# AMU-S05-V00-CAN2.net
KiCad netlist of a schematic drawn in Altium Designer
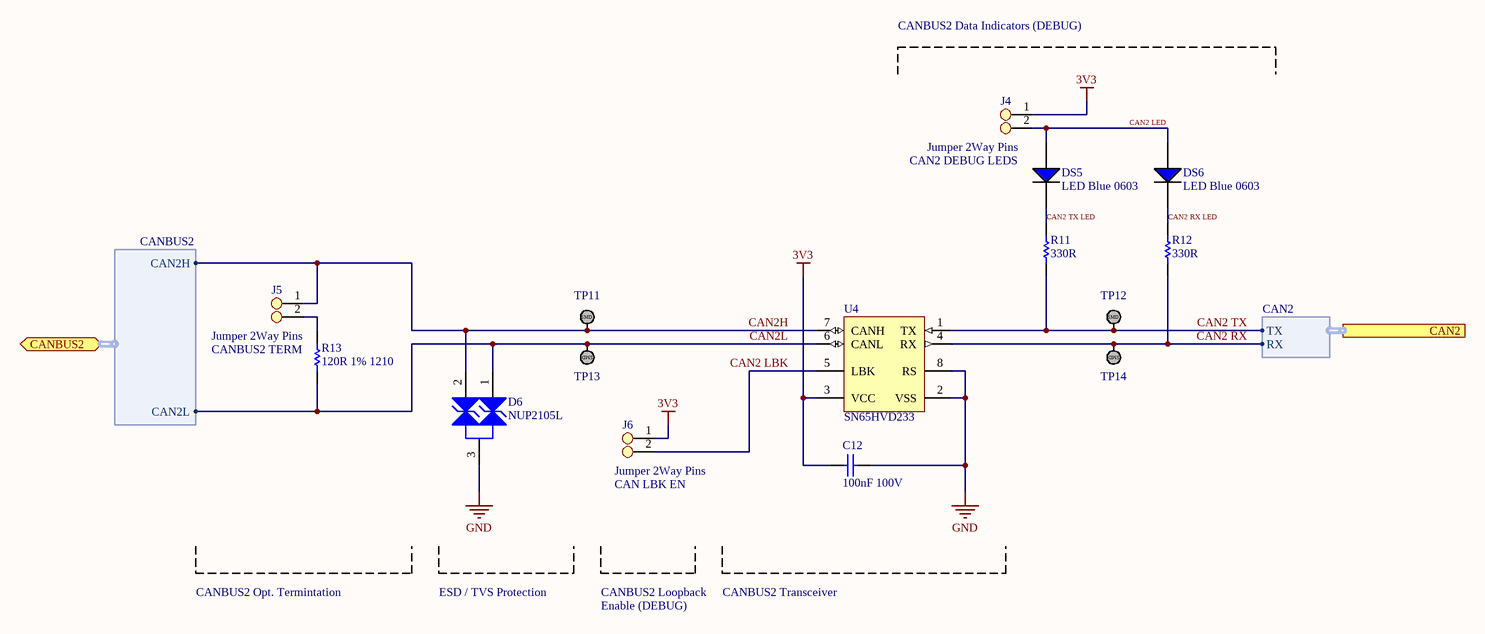
[diagram p0: AMU-S05-V00-CAN2.SchDoc]

(export (version "E")
  (design (tool "Eeschema 10.0.6"))
  (components
    (comp (ref "C12")
      (value "100nF 100V")
      (footprint "Cap_Ceramic_0603")
      (description "Capacitor, Ceramic, SMD, 100nF, 100V, 5%, X7R, 0603")
      (libsource (lib "StandardCapacitors") (part "100nF 100V 5% X7R 0603"))
    )
    (comp (ref "D6")
      (value "NUP2105L")
      (footprint "NUP2105L")
      (libsource (lib "QUTMS_CANLibrary") (part "NUP2105L"))
    )
    (comp (ref "DS5")
      (value "LED Blue 0603")
      (footprint "LED BLUE 0603")
      (libsource (lib "QUTMS_LEDLibrary") (part "LED BLUE 0603"))
    )
    (comp (ref "DS6")
      (value "LED Blue 0603")
      (footprint "LED BLUE 0603")
      (libsource (lib "QUTMS_LEDLibrary") (part "LED BLUE 0603"))
    )
    (comp (ref "J4")
      (value "Jumper 2Way Pins")
      (footprint "Jumper_2Way_Pin")
      (description "Jumper 2Way Side Pins")
      (libsource (lib "QUTMS_JumperLibrary") (part "Jumper 2Way Side Pins"))
    )
    (comp (ref "J5")
      (value "Jumper 2Way Pins")
      (footprint "Jumper_2Way_Pin")
      (description "Jumper 2Way Side Pins")
      (libsource (lib "QUTMS_JumperLibrary") (part "Jumper 2Way Side Pins"))
    )
    (comp (ref "J6")
      (value "Jumper 2Way Pins")
      (footprint "Jumper_2Way_Pin")
      (description "Jumper 2Way Side Pins")
      (libsource (lib "QUTMS_JumperLibrary") (part "Jumper 2Way Side Pins"))
    )
    (comp (ref "R11")
      (value "330R")
      (footprint "Res_ThinFilm_0603")
      (description "Resistor, SMD, 330R, 0.1W, 5%, 0603")
      (libsource (lib "StandardResistors") (part "330R 5% 0603"))
    )
    (comp (ref "R12")
      (value "330R")
      (footprint "Res_ThinFilm_0603")
      (description "Resistor, SMD, 330R, 0.1W, 5%, 0603")
      (libsource (lib "StandardResistors") (part "330R 5% 0603"))
    )
    (comp (ref "R13")
      (value "120R 1% 1210")
      (footprint "Res_ThinFilm_1210")
      (description "Resistor, SMD, 120R, 0.25W, 1%, 1210")
      (libsource (lib "StandardResistors") (part "120R 1% 1210"))
    )
    (comp (ref "TP11")
      (value "TestPoint_SMD")
      (footprint "TestPointSMD")
      (libsource (lib "StandardTest") (part "TestPoint_SMD"))
    )
    (comp (ref "TP12")
      (value "TestPoint_SMD")
      (footprint "TestPointSMD")
      (libsource (lib "StandardTest") (part "TestPoint_SMD"))
    )
    (comp (ref "TP13")
      (value "TestPoint_SMD")
      (footprint "TestPointSMD")
      (libsource (lib "StandardTest") (part "TestPoint_SMD"))
    )
    (comp (ref "TP14")
      (value "TestPoint_SMD")
      (footprint "TestPointSMD")
      (libsource (lib "StandardTest") (part "TestPoint_SMD"))
    )
    (comp (ref "U4")
      (value "SN65HVD233")
      (footprint "SN65HVD233DR")
      (libsource (lib "QUTMS_CANLibrary") (part "SN65HVD233"))
    )
  )
  (nets
    (net (code "3") (name "/CAN2 LBK") (class "Default")
      (node (ref "J6") (pin "2") (pinfunction "2_2") (pintype "passive"))
      (node (ref "U4") (pin "5") (pinfunction "LBK_5") (pintype "passive"))
    )
    (net (code "4") (name "/CAN2 LED") (class "Default")
      (node (ref "DS5") (pin "1") (pinfunction "A_1") (pintype "passive"))
      (node (ref "DS6") (pin "1") (pinfunction "A_1") (pintype "passive"))
      (node (ref "J4") (pin "2") (pinfunction "2_2") (pintype "passive"))
    )
    (net (code "5") (name "/CAN2 RX") (class "Default")
      (node (ref "R12") (pin "1") (pinfunction "1_1") (pintype "passive"))
      (node (ref "TP14") (pin "1") (pinfunction "1_1") (pintype "passive"))
      (node (ref "U4") (pin "4") (pinfunction "RX_4") (pintype "output"))
    )
    (net (code "6") (name "/CAN2 RX LED") (class "Default")
      (node (ref "DS6") (pin "2") (pinfunction "C_2") (pintype "passive"))
      (node (ref "R12") (pin "2") (pinfunction "2_2") (pintype "passive"))
    )
    (net (code "7") (name "/CAN2 TX") (class "Default")
      (node (ref "R11") (pin "1") (pinfunction "1_1") (pintype "passive"))
      (node (ref "TP12") (pin "1") (pinfunction "1_1") (pintype "passive"))
      (node (ref "U4") (pin "1") (pinfunction "TX_1") (pintype "input"))
    )
    (net (code "8") (name "/CAN2 TX LED") (class "Default")
      (node (ref "DS5") (pin "2") (pinfunction "C_2") (pintype "passive"))
      (node (ref "R11") (pin "2") (pinfunction "2_2") (pintype "passive"))
    )
    (net (code "9") (name "/CAN2H") (class "Default")
      (node (ref "D6") (pin "2") (pinfunction "2_2") (pintype "passive"))
      (node (ref "J5") (pin "1") (pinfunction "1_1") (pintype "passive"))
      (node (ref "TP11") (pin "1") (pinfunction "1_1") (pintype "passive"))
      (node (ref "U4") (pin "7") (pinfunction "CANH_7") (pintype "bidirectional"))
    )
    (net (code "10") (name "/CAN2L") (class "Default")
      (node (ref "D6") (pin "1") (pinfunction "1_1") (pintype "passive"))
      (node (ref "R13") (pin "1") (pinfunction "1_1") (pintype "passive"))
      (node (ref "TP13") (pin "1") (pinfunction "1_1") (pintype "passive"))
      (node (ref "U4") (pin "6") (pinfunction "CANL_6") (pintype "bidirectional"))
    )
    (net (code "13") (name "3V3") (class "Default")
      (node (ref "C12") (pin "2") (pinfunction "2_2") (pintype "passive"))
      (node (ref "J4") (pin "1") (pinfunction "1_1") (pintype "passive"))
      (node (ref "J6") (pin "1") (pinfunction "1_1") (pintype "passive"))
      (node (ref "U4") (pin "3") (pinfunction "VCC_3") (pintype "passive"))
    )
    (net (code "14") (name "GND") (class "Default")
      (node (ref "C12") (pin "1") (pinfunction "1_1") (pintype "passive"))
      (node (ref "D6") (pin "3") (pinfunction "3_3") (pintype "passive"))
      (node (ref "U4") (pin "2") (pinfunction "VSS_2") (pintype "passive"))
      (node (ref "U4") (pin "8") (pinfunction "RS_8") (pintype "passive"))
    )
    (net (code "15") (name "Net-(J5-Pad2)") (class "Default")
      (node (ref "J5") (pin "2") (pinfunction "2_2") (pintype "passive"))
      (node (ref "R13") (pin "2") (pinfunction "2_2") (pintype "passive"))
    )
  )
)
